# ADC_Interface.net
KiCad netlist of a schematic drawn in Altium Designer
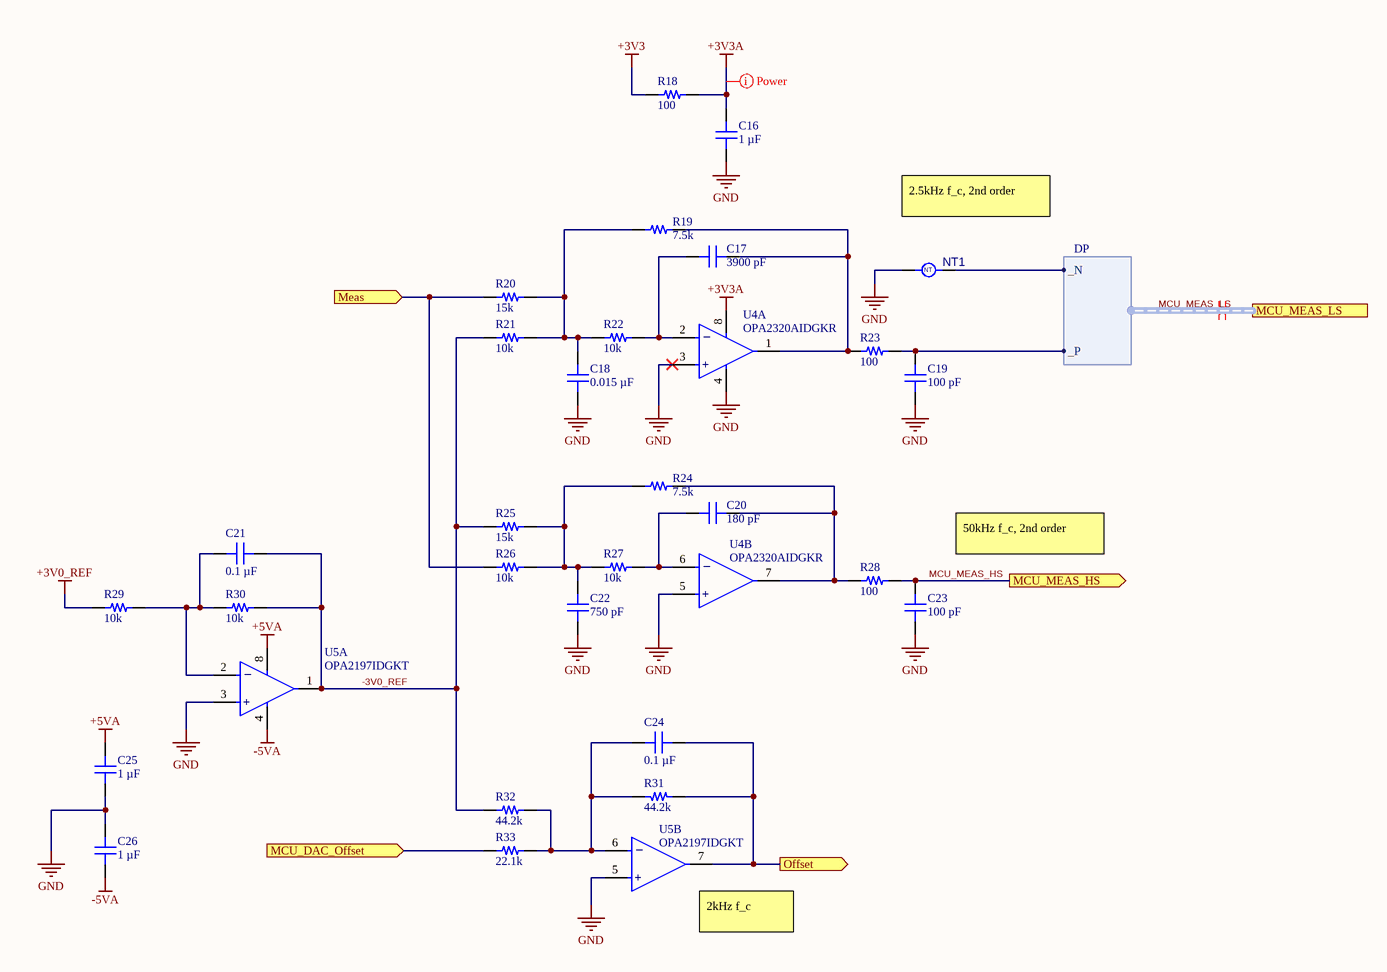
[diagram p0: ADC_Interface.SchDoc]

(export (version "E")
  (design (tool "Eeschema 10.0.6"))
  (components
    (comp (ref "C16")
      (value "1 µF")
      (footprint "MURATA GRM155 0402_1005")
      (description "CAP CER 1UF 25V X5R 0402")
      (fields
        (field (name "PART NUMBER") "GRM155R61E105MA12D")
        (field (name "MANUFACTURER") "Murata Electronics")
      )
      (libsource (lib "Celestial Altium Library - altium_library") (part "Capacitor"))
    )
    (comp (ref "C17")
      (value "3900 pF")
      (footprint "MURATA GRM155 0402_1005")
      (description "CAP CER 3900PF 50V C0G/NP0 0402")
      (fields
        (field (name "PART NUMBER") "GRM1555C1H392GE01D")
        (field (name "MANUFACTURER") "Murata Electronics")
      )
      (libsource (lib "Celestial Altium Library - altium_library") (part "Capacitor"))
    )
    (comp (ref "C18")
      (value "0.015 µF")
      (footprint "MURATA GCM155 0402_1005")
      (description "CAP CER 0.015UF 50V X7R 0402")
      (fields
        (field (name "PART NUMBER") "GCM155R71H153KA55J")
        (field (name "MANUFACTURER") "Murata Electronics")
      )
      (libsource (lib "Celestial Altium Library - altium_library") (part "Capacitor"))
    )
    (comp (ref "C19")
      (value "100 pF")
      (footprint "MURATA GCM155 0402_1005")
      (description "CAP CER 100PF 50V C0G/NP0 0402")
      (fields
        (field (name "PART NUMBER") "GCM1555C1H101FA16D")
        (field (name "MANUFACTURER") "Murata Electronics")
      )
      (libsource (lib "Celestial Altium Library - altium_library") (part "Capacitor"))
    )
    (comp (ref "C20")
      (value "180 pF")
      (footprint "MURATA GCM155 0402_1005")
      (description "CAP CER 180PF 50V C0G/NP0 0402")
      (fields
        (field (name "PART NUMBER") "GCM1555C1H181JA16J")
        (field (name "MANUFACTURER") "Murata Electronics")
      )
      (libsource (lib "Celestial Altium Library - altium_library") (part "Capacitor"))
    )
    (comp (ref "C21")
      (value "0.1 µF")
      (footprint "MURATA GRM155 0402_1005")
      (description "CAP CER 0.1UF 50V X5R 0402")
      (fields
        (field (name "PART NUMBER") "GRM155R61H104KE19D")
        (field (name "MANUFACTURER") "Murata Electronics")
      )
      (libsource (lib "Celestial Altium Library - altium_library") (part "Capacitor"))
    )
    (comp (ref "C22")
      (value "750 pF")
      (footprint "MURATA GCM155 0402_1005")
      (description "CAP CER 750PF 50V C0G/NP0 0402")
      (fields
        (field (name "PART NUMBER") "GCM1555C1H751GA16D")
        (field (name "MANUFACTURER") "Murata Electronics")
      )
      (libsource (lib "Celestial Altium Library - altium_library") (part "Capacitor"))
    )
    (comp (ref "C23")
      (value "100 pF")
      (footprint "MURATA GCM155 0402_1005")
      (description "CAP CER 100PF 50V C0G/NP0 0402")
      (fields
        (field (name "PART NUMBER") "GCM1555C1H101FA16D")
        (field (name "MANUFACTURER") "Murata Electronics")
      )
      (libsource (lib "Celestial Altium Library - altium_library") (part "Capacitor"))
    )
    (comp (ref "C24")
      (value "0.1 µF")
      (footprint "MURATA GRM155 0402_1005")
      (description "CAP CER 0.1UF 50V X5R 0402")
      (fields
        (field (name "PART NUMBER") "GRM155R61H104KE19D")
        (field (name "MANUFACTURER") "Murata Electronics")
      )
      (libsource (lib "Celestial Altium Library - altium_library") (part "Capacitor"))
    )
    (comp (ref "C25")
      (value "1 µF")
      (footprint "MURATA GRM155 0402_1005")
      (description "CAP CER 1UF 25V X5R 0402")
      (fields
        (field (name "PART NUMBER") "GRM155R61E105MA12D")
        (field (name "MANUFACTURER") "Murata Electronics")
      )
      (libsource (lib "Celestial Altium Library - altium_library") (part "Capacitor"))
    )
    (comp (ref "C26")
      (value "1 µF")
      (footprint "MURATA GRM155 0402_1005")
      (description "CAP CER 1UF 25V X5R 0402")
      (fields
        (field (name "PART NUMBER") "GRM155R61E105MA12D")
        (field (name "MANUFACTURER") "Murata Electronics")
      )
      (libsource (lib "Celestial Altium Library - altium_library") (part "Capacitor"))
    )
    (comp (ref "NT1")
      (value "Net Tie 10x8mil")
      (footprint "New footprint 1")
      (libsource (lib "Flycatcher Labs") (part "CMP-00022-00002-2"))
    )
    (comp (ref "R18")
      (value "100")
      (footprint "RES 0402_1005")
      (description "RES SMD 100 OHM 1% 1/16W 0402")
      (fields (field (name "PART NUMBER") "CRCW0402100RFKEE") (field (name "MANUFACTURER") "Vishay Dale"))
      (libsource (lib "Celestial Altium Library - altium_library") (part "Resistor"))
    )
    (comp (ref "R19")
      (value "7.5k")
      (footprint "RES 0402_1005")
      (description "RES SMD 7.5K OHM 0.1% 1/16W 0402")
      (fields
        (field (name "PART NUMBER") "ERA-2ARB752X")
        (field (name "MANUFACTURER") "Panasonic Electronic Components")
      )
      (libsource (lib "Celestial Altium Library - altium_library") (part "Resistor"))
    )
    (comp (ref "R20")
      (value "15k")
      (footprint "RES 0402_1005")
      (description "RES SMD 15K OHM 0.1% 1/16W 0402")
      (fields
        (field (name "PART NUMBER") "ERA-2AEB153X")
        (field (name "MANUFACTURER") "Panasonic Electronic Components")
      )
      (libsource (lib "Celestial Altium Library - altium_library") (part "Resistor"))
    )
    (comp (ref "R21")
      (value "10k")
      (footprint "RES 0402_1005")
      (description "RES 10K OHM 0.05% 1/10W 0402")
      (fields
        (field (name "PART NUMBER") "ERA-2VRW1002X")
        (field (name "MANUFACTURER") "Panasonic Electronic Components")
      )
      (libsource (lib "Celestial Altium Library - altium_library") (part "Resistor"))
    )
    (comp (ref "R22")
      (value "10k")
      (footprint "RES 0402_1005")
      (description "RES 10K OHM 0.05% 1/10W 0402")
      (fields
        (field (name "PART NUMBER") "ERA-2VRW1002X")
        (field (name "MANUFACTURER") "Panasonic Electronic Components")
      )
      (libsource (lib "Celestial Altium Library - altium_library") (part "Resistor"))
    )
    (comp (ref "R23")
      (value "100")
      (footprint "RES 0402_1005")
      (description "RES SMD 100 OHM 1% 1/16W 0402")
      (fields (field (name "PART NUMBER") "CRCW0402100RFKEE") (field (name "MANUFACTURER") "Vishay Dale"))
      (libsource (lib "Celestial Altium Library - altium_library") (part "Resistor"))
    )
    (comp (ref "R24")
      (value "7.5k")
      (footprint "RES 0402_1005")
      (description "RES SMD 7.5K OHM 0.1% 1/16W 0402")
      (fields
        (field (name "PART NUMBER") "ERA-2ARB752X")
        (field (name "MANUFACTURER") "Panasonic Electronic Components")
      )
      (libsource (lib "Celestial Altium Library - altium_library") (part "Resistor"))
    )
    (comp (ref "R25")
      (value "15k")
      (footprint "RES 0402_1005")
      (description "RES SMD 15K OHM 0.1% 1/16W 0402")
      (fields
        (field (name "PART NUMBER") "ERA-2AEB153X")
        (field (name "MANUFACTURER") "Panasonic Electronic Components")
      )
      (libsource (lib "Celestial Altium Library - altium_library") (part "Resistor"))
    )
    (comp (ref "R26")
      (value "10k")
      (footprint "RES 0402_1005")
      (description "RES 10K OHM 0.05% 1/10W 0402")
      (fields
        (field (name "PART NUMBER") "ERA-2VRW1002X")
        (field (name "MANUFACTURER") "Panasonic Electronic Components")
      )
      (libsource (lib "Celestial Altium Library - altium_library") (part "Resistor"))
    )
    (comp (ref "R27")
      (value "10k")
      (footprint "RES 0402_1005")
      (description "RES 10K OHM 0.05% 1/10W 0402")
      (fields
        (field (name "PART NUMBER") "ERA-2VRW1002X")
        (field (name "MANUFACTURER") "Panasonic Electronic Components")
      )
      (libsource (lib "Celestial Altium Library - altium_library") (part "Resistor"))
    )
    (comp (ref "R28")
      (value "100")
      (footprint "RES 0402_1005")
      (description "RES SMD 100 OHM 1% 1/16W 0402")
      (fields (field (name "PART NUMBER") "CRCW0402100RFKEE") (field (name "MANUFACTURER") "Vishay Dale"))
      (libsource (lib "Celestial Altium Library - altium_library") (part "Resistor"))
    )
    (comp (ref "R29")
      (value "10k")
      (footprint "RES 0402_1005")
      (description "RES 10K OHM 0.05% 1/10W 0402")
      (fields
        (field (name "PART NUMBER") "ERA-2VRW1002X")
        (field (name "MANUFACTURER") "Panasonic Electronic Components")
      )
      (libsource (lib "Celestial Altium Library - altium_library") (part "Resistor"))
    )
    (comp (ref "R30")
      (value "10k")
      (footprint "RES 0402_1005")
      (description "RES 10K OHM 0.05% 1/10W 0402")
      (fields
        (field (name "PART NUMBER") "ERA-2VRW1002X")
        (field (name "MANUFACTURER") "Panasonic Electronic Components")
      )
      (libsource (lib "Celestial Altium Library - altium_library") (part "Resistor"))
    )
    (comp (ref "R31")
      (value "44.2k")
      (footprint "RES 0402_1005")
      (description "RES SMD 44.2KOHM 0.1% 1/16W 0402")
      (fields
        (field (name "PART NUMBER") "ERA-2ARB4422X")
        (field (name "MANUFACTURER") "Panasonic Electronic Components")
      )
      (libsource (lib "Celestial Altium Library - altium_library") (part "Resistor"))
    )
    (comp (ref "R32")
      (value "44.2k")
      (footprint "RES 0402_1005")
      (description "RES SMD 44.2KOHM 0.1% 1/16W 0402")
      (fields
        (field (name "PART NUMBER") "ERA-2ARB4422X")
        (field (name "MANUFACTURER") "Panasonic Electronic Components")
      )
      (libsource (lib "Celestial Altium Library - altium_library") (part "Resistor"))
    )
    (comp (ref "R33")
      (value "22.1k")
      (footprint "RES 0402_1005")
      (description "RES SMD 22.1KOHM 0.1% 1/16W 0402")
      (fields
        (field (name "PART NUMBER") "ERA-2AEB2212X")
        (field (name "MANUFACTURER") "Panasonic Electronic Components")
      )
      (libsource (lib "Celestial Altium Library - altium_library") (part "Resistor"))
    )
    (comp (ref "U4")
      (value "OPA2320AIDGKR")
      (footprint "FP-DGK0008A-MFG")
      (description "Op Amp Dual Precision Amplifier R-R I/O ±2.75V/5.5V 8-Pin VSSOP T/R")
      (libsource (lib "Flycatcher Labs") (part "Dual Op Amp"))
    )
    (comp (ref "U5")
      (value "OPA2197IDGKT")
      (footprint "FP-DGK0008A-MFG")
      (description "Dual 36-V, precision, rail-to-rail input output, low offset voltage op amp 8-VSSOP -40 to 125")
      (libsource (lib "Flycatcher Labs") (part "Dual Op Amp"))
    )
  )
  (nets
    (net (code "2") (name "+3V0_REF") (class "Default")
      (node (ref "R29") (pin "2") (pinfunction "2_2") (pintype "passive"))
    )
    (net (code "3") (name "+3V3") (class "Default")
      (node (ref "R18") (pin "1") (pinfunction "1_1") (pintype "passive"))
    )
    (net (code "4") (name "+3V3A") (class "Default")
      (node (ref "C16") (pin "2") (pinfunction "2_2") (pintype "passive"))
      (node (ref "R18") (pin "2") (pinfunction "2_2") (pintype "passive"))
      (node (ref "U4") (pin "8") (pinfunction "V+_8") (pintype "power_in"))
    )
    (net (code "5") (name "+5VA") (class "Default")
      (node (ref "C25") (pin "2") (pinfunction "2_2") (pintype "passive"))
      (node (ref "U5") (pin "8") (pinfunction "V+_8") (pintype "power_in"))
    )
    (net (code "6") (name "-5VA") (class "Default")
      (node (ref "C26") (pin "1") (pinfunction "1_1") (pintype "passive"))
      (node (ref "U5") (pin "4") (pinfunction "V-_4") (pintype "power_in"))
    )
    (net (code "7") (name "/-3V0_REF") (class "Default")
      (node (ref "C21") (pin "1") (pinfunction "1_1") (pintype "passive"))
      (node (ref "R21") (pin "2") (pinfunction "2_2") (pintype "passive"))
      (node (ref "R25") (pin "1") (pinfunction "1_1") (pintype "passive"))
      (node (ref "R30") (pin "1") (pinfunction "1_1") (pintype "passive"))
      (node (ref "R32") (pin "1") (pinfunction "1_1") (pintype "passive"))
      (node (ref "U5") (pin "1") (pinfunction "OUTA_1") (pintype "passive"))
    )
    (net (code "8") (name "/MCU_DAC_Offset") (class "Default")
      (node (ref "R33") (pin "1") (pinfunction "1_1") (pintype "passive"))
    )
    (net (code "9") (name "/MCU_MEAS_HS") (class "Default")
      (node (ref "C23") (pin "2") (pinfunction "2_2") (pintype "passive"))
      (node (ref "R28") (pin "2") (pinfunction "2_2") (pintype "passive"))
    )
    (net (code "11") (name "/Meas") (class "Default")
      (node (ref "R20") (pin "1") (pinfunction "1_1") (pintype "passive"))
      (node (ref "R26") (pin "2") (pinfunction "2_2") (pintype "passive"))
    )
    (net (code "12") (name "/Offset") (class "Default")
      (node (ref "C24") (pin "1") (pinfunction "1_1") (pintype "passive"))
      (node (ref "R31") (pin "2") (pinfunction "2_2") (pintype "passive"))
      (node (ref "U5") (pin "7") (pinfunction "OUTB_7") (pintype "passive"))
    )
    (net (code "13") (name "/_N") (class "Default")
      (node (ref "NT1") (pin "2") (pinfunction "2_2") (pintype "passive"))
    )
    (net (code "14") (name "/_P") (class "Default")
      (node (ref "C19") (pin "2") (pinfunction "2_2") (pintype "passive"))
      (node (ref "R23") (pin "2") (pinfunction "2_2") (pintype "passive"))
    )
    (net (code "15") (name "GND") (class "Default")
      (node (ref "C16") (pin "1") (pinfunction "1_1") (pintype "passive"))
      (node (ref "C18") (pin "1") (pinfunction "1_1") (pintype "passive"))
      (node (ref "C19") (pin "1") (pinfunction "1_1") (pintype "passive"))
      (node (ref "C22") (pin "1") (pinfunction "1_1") (pintype "passive"))
      (node (ref "C23") (pin "1") (pinfunction "1_1") (pintype "passive"))
      (node (ref "C25") (pin "1") (pinfunction "1_1") (pintype "passive"))
      (node (ref "C26") (pin "2") (pinfunction "2_2") (pintype "passive"))
      (node (ref "NT1") (pin "1") (pinfunction "1_1") (pintype "passive"))
      (node (ref "U4") (pin "3") (pinfunction "+INA_3") (pintype "tri_state"))
      (node (ref "U4") (pin "4") (pinfunction "V-_4") (pintype "power_in"))
      (node (ref "U4") (pin "5") (pinfunction "+INB_5") (pintype "tri_state"))
      (node (ref "U5") (pin "3") (pinfunction "+INA_3") (pintype "tri_state"))
      (node (ref "U5") (pin "5") (pinfunction "+INB_5") (pintype "tri_state"))
    )
    (net (code "16") (name "Net-(C18-Pad2)") (class "Default")
      (node (ref "C18") (pin "2") (pinfunction "2_2") (pintype "passive"))
      (node (ref "R19") (pin "1") (pinfunction "1_1") (pintype "passive"))
      (node (ref "R20") (pin "2") (pinfunction "2_2") (pintype "passive"))
      (node (ref "R21") (pin "1") (pinfunction "1_1") (pintype "passive"))
      (node (ref "R22") (pin "2") (pinfunction "2_2") (pintype "passive"))
    )
    (net (code "17") (name "Net-(C22-Pad2)") (class "Default")
      (node (ref "C22") (pin "2") (pinfunction "2_2") (pintype "passive"))
      (node (ref "R24") (pin "1") (pinfunction "1_1") (pintype "passive"))
      (node (ref "R25") (pin "2") (pinfunction "2_2") (pintype "passive"))
      (node (ref "R26") (pin "1") (pinfunction "1_1") (pintype "passive"))
      (node (ref "R27") (pin "2") (pinfunction "2_2") (pintype "passive"))
    )
    (net (code "18") (name "Net-(U4A--INA)") (class "Default")
      (node (ref "C17") (pin "1") (pinfunction "1_1") (pintype "passive"))
      (node (ref "R22") (pin "1") (pinfunction "1_1") (pintype "passive"))
      (node (ref "U4") (pin "2") (pinfunction "-INA_2") (pintype "tri_state"))
    )
    (net (code "19") (name "Net-(U4A-OUTA)") (class "Default")
      (node (ref "C17") (pin "2") (pinfunction "2_2") (pintype "passive"))
      (node (ref "R19") (pin "2") (pinfunction "2_2") (pintype "passive"))
      (node (ref "R23") (pin "1") (pinfunction "1_1") (pintype "passive"))
      (node (ref "U4") (pin "1") (pinfunction "OUTA_1") (pintype "passive"))
    )
    (net (code "20") (name "Net-(U4B--INB)") (class "Default")
      (node (ref "C20") (pin "1") (pinfunction "1_1") (pintype "passive"))
      (node (ref "R27") (pin "1") (pinfunction "1_1") (pintype "passive"))
      (node (ref "U4") (pin "6") (pinfunction "-INB_6") (pintype "tri_state"))
    )
    (net (code "21") (name "Net-(U4B-OUTB)") (class "Default")
      (node (ref "C20") (pin "2") (pinfunction "2_2") (pintype "passive"))
      (node (ref "R24") (pin "2") (pinfunction "2_2") (pintype "passive"))
      (node (ref "R28") (pin "1") (pinfunction "1_1") (pintype "passive"))
      (node (ref "U4") (pin "7") (pinfunction "OUTB_7") (pintype "passive"))
    )
    (net (code "22") (name "Net-(U5A--INA)") (class "Default")
      (node (ref "C21") (pin "2") (pinfunction "2_2") (pintype "passive"))
      (node (ref "R29") (pin "1") (pinfunction "1_1") (pintype "passive"))
      (node (ref "R30") (pin "2") (pinfunction "2_2") (pintype "passive"))
      (node (ref "U5") (pin "2") (pinfunction "-INA_2") (pintype "tri_state"))
    )
    (net (code "23") (name "Net-(U5B--INB)") (class "Default")
      (node (ref "C24") (pin "2") (pinfunction "2_2") (pintype "passive"))
      (node (ref "R31") (pin "1") (pinfunction "1_1") (pintype "passive"))
      (node (ref "R32") (pin "2") (pinfunction "2_2") (pintype "passive"))
      (node (ref "R33") (pin "2") (pinfunction "2_2") (pintype "passive"))
      (node (ref "U5") (pin "6") (pinfunction "-INB_6") (pintype "tri_state"))
    )
  )
)
